# FAN_Boardv1_RelayAlarm_040116.net
KiCad netlist of a schematic drawn in Altium Designer
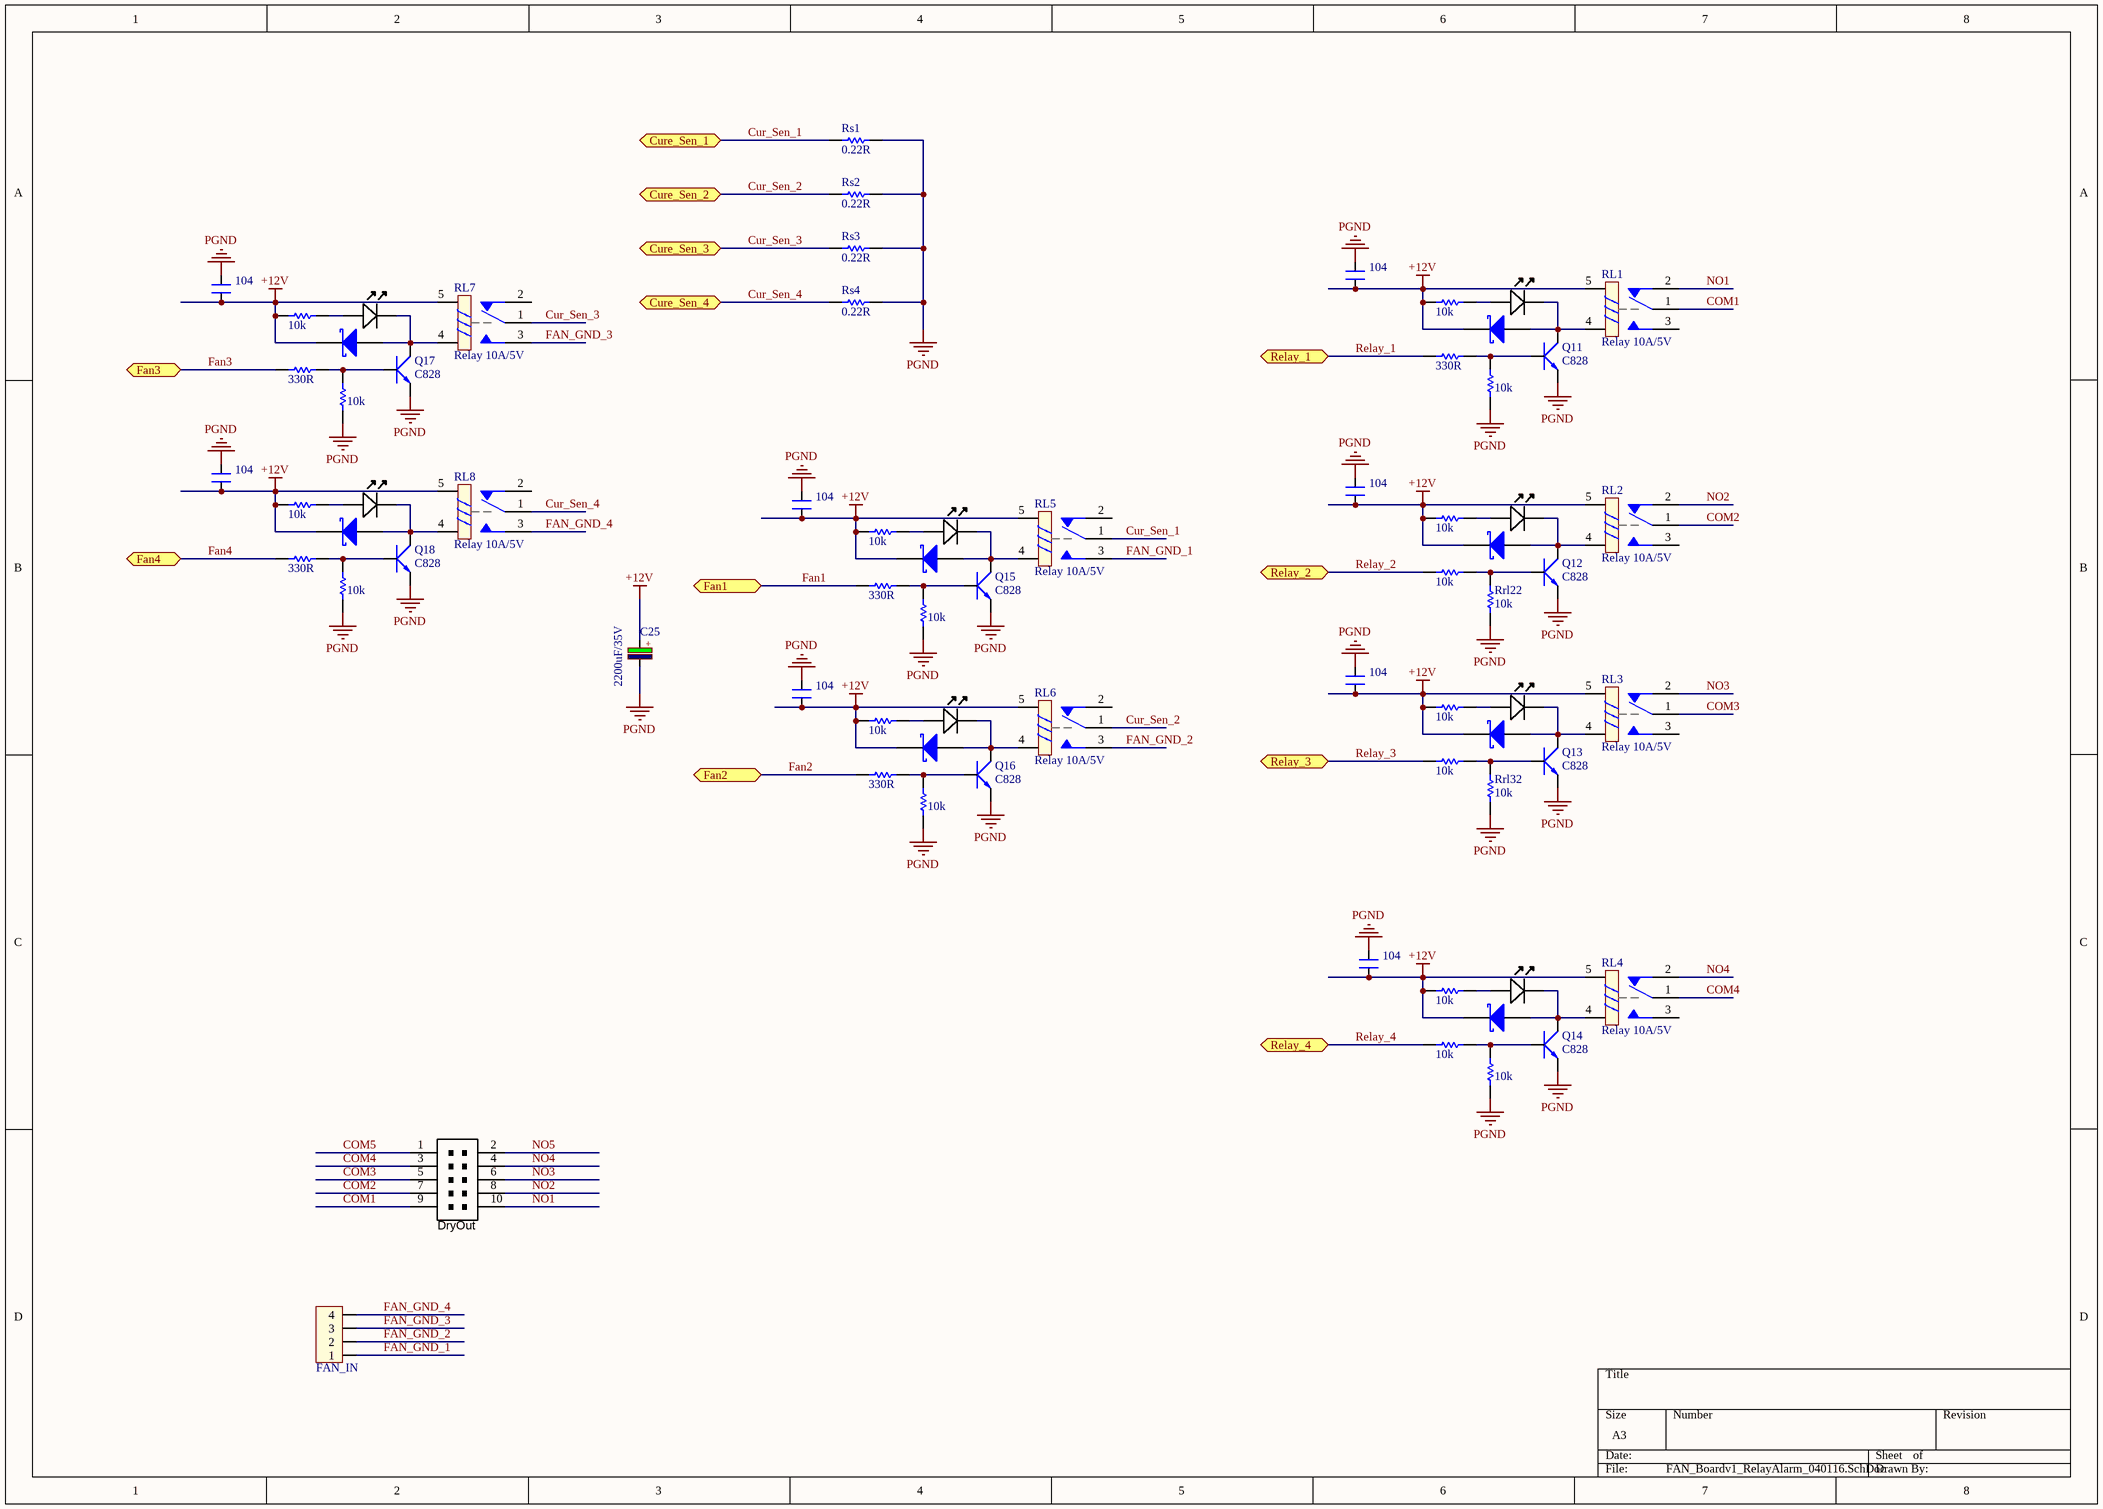
[diagram p0: FAN_Boardv1_RelayAlarm_040116.SchDoc]

(export (version "E")
  (design (tool "Eeschema 10.0.6"))
  (components
    (comp (ref "C25")
      (value "2200uF/35V")
      (footprint "heromap:CP_1000uF_25V")
      (description "Cap 1000uF/16V - 220uF/50V")
      (libsource (lib "heromap") (part "CP4"))
    )
    (comp (ref "Crl1")
      (value "104")
      (footprint "CAPC2012N_F")
      (fields (field (name "Comment") "CAP NP"))
      (libsource (lib "Tuan") (part "CAP NP"))
    )
    (comp (ref "Crl2")
      (value "104")
      (footprint "CAPC2012N_F")
      (fields (field (name "Comment") "CAP NP"))
      (libsource (lib "Tuan") (part "CAP NP"))
    )
    (comp (ref "Crl3")
      (value "104")
      (footprint "CAPC2012N_F")
      (fields (field (name "Comment") "CAP NP"))
      (libsource (lib "Tuan") (part "CAP NP"))
    )
    (comp (ref "Crl4")
      (value "104")
      (footprint "CAPC2012N_F")
      (fields (field (name "Comment") "CAP NP"))
      (libsource (lib "Tuan") (part "CAP NP"))
    )
    (comp (ref "Crl5")
      (value "104")
      (footprint "CAPC2012N_F")
      (fields (field (name "Comment") "CAP NP"))
      (libsource (lib "Tuan") (part "CAP NP"))
    )
    (comp (ref "Crl6")
      (value "104")
      (footprint "CAPC2012N_F")
      (fields (field (name "Comment") "CAP NP"))
      (libsource (lib "Tuan") (part "CAP NP"))
    )
    (comp (ref "Crl7")
      (value "104")
      (footprint "CAPC2012N_F")
      (fields (field (name "Comment") "CAP NP"))
      (libsource (lib "Tuan") (part "CAP NP"))
    )
    (comp (ref "Crl8")
      (value "104")
      (footprint "CAPC2012N_F")
      (fields (field (name "Comment") "CAP NP"))
      (libsource (lib "Tuan") (part "CAP NP"))
    )
    (comp (ref "D11") (value "Diode") (footprint "DO-214AC") (libsource (lib "Tuan") (part "Diode")))
    (comp (ref "D12") (value "Diode") (footprint "DO-214AC") (libsource (lib "Tuan") (part "Diode")))
    (comp (ref "D13") (value "Diode") (footprint "DO-214AC") (libsource (lib "Tuan") (part "Diode")))
    (comp (ref "D14") (value "Diode") (footprint "DO-214AC") (libsource (lib "Tuan") (part "Diode")))
    (comp (ref "D15") (value "Diode") (footprint "DO-214AC") (libsource (lib "Tuan") (part "Diode")))
    (comp (ref "D16") (value "Diode") (footprint "DO-214AC") (libsource (lib "Tuan") (part "Diode")))
    (comp (ref "D17") (value "Diode") (footprint "DO-214AC") (libsource (lib "Tuan") (part "Diode")))
    (comp (ref "D18") (value "Diode") (footprint "DO-214AC") (libsource (lib "Tuan") (part "Diode")))
    (comp (ref "DryOut")
      (value "shrouded box header")
      (footprint "10P_PCB_HEADER_BRD_MNT")
      (description "Header THD 10 POS Double-row 2.54mm pitch")
      (libsource (lib "PBL - Connectors") (part "CONN_HEADER_2x5P_0.100in_Male"))
    )
    (comp (ref "E1")
      (value "Blue")
      (footprint "LED-0805-A")
      (description "LED 0805 SMD Blue 100mcd 470nm")
      (libsource (lib "PBL - Light Sources") (part "LED_SMD_Blue_0805_100mcd"))
    )
    (comp (ref "E2")
      (value "Blue")
      (footprint "LED-0805-A")
      (description "LED 0805 SMD Blue 100mcd 470nm")
      (libsource (lib "PBL - Light Sources") (part "LED_SMD_Blue_0805_100mcd"))
    )
    (comp (ref "E3")
      (value "Blue")
      (footprint "LED-0805-A")
      (description "LED 0805 SMD Blue 100mcd 470nm")
      (libsource (lib "PBL - Light Sources") (part "LED_SMD_Blue_0805_100mcd"))
    )
    (comp (ref "E4")
      (value "Blue")
      (footprint "LED-0805-A")
      (description "LED 0805 SMD Blue 100mcd 470nm")
      (libsource (lib "PBL - Light Sources") (part "LED_SMD_Blue_0805_100mcd"))
    )
    (comp (ref "E5")
      (value "Blue")
      (footprint "LED-0805-A")
      (description "LED 0805 SMD Blue 100mcd 470nm")
      (libsource (lib "PBL - Light Sources") (part "LED_SMD_Blue_0805_100mcd"))
    )
    (comp (ref "E6")
      (value "Blue")
      (footprint "LED-0805-A")
      (description "LED 0805 SMD Blue 100mcd 470nm")
      (libsource (lib "PBL - Light Sources") (part "LED_SMD_Blue_0805_100mcd"))
    )
    (comp (ref "E7")
      (value "Blue")
      (footprint "LED-0805-A")
      (description "LED 0805 SMD Blue 100mcd 470nm")
      (libsource (lib "PBL - Light Sources") (part "LED_SMD_Blue_0805_100mcd"))
    )
    (comp (ref "E8")
      (value "Blue")
      (footprint "LED-0805-A")
      (description "LED 0805 SMD Blue 100mcd 470nm")
      (libsource (lib "PBL - Light Sources") (part "LED_SMD_Blue_0805_100mcd"))
    )
    (comp (ref "FAN_IN")
      (value "Header 4")
      (footprint "heromap:HED4")
      (description "Header 4 (Green)")
      (libsource (lib "heromap") (part "Hed4"))
    )
    (comp (ref "Q11")
      (value "C828")
      (footprint "SOT23 TOP")
      (description "Transistor C828 C1815....")
      (libsource (lib "Tuan") (part "NPN"))
    )
    (comp (ref "Q12")
      (value "C828")
      (footprint "SOT23 TOP")
      (description "Transistor C828 C1815....")
      (libsource (lib "Tuan") (part "NPN"))
    )
    (comp (ref "Q13")
      (value "C828")
      (footprint "SOT23 TOP")
      (description "Transistor C828 C1815....")
      (libsource (lib "Tuan") (part "NPN"))
    )
    (comp (ref "Q14")
      (value "C828")
      (footprint "SOT23 TOP")
      (description "Transistor C828 C1815....")
      (libsource (lib "Tuan") (part "NPN"))
    )
    (comp (ref "Q15")
      (value "C828")
      (footprint "SOT23 TOP")
      (description "Transistor C828 C1815....")
      (libsource (lib "Tuan") (part "NPN"))
    )
    (comp (ref "Q16")
      (value "C828")
      (footprint "SOT23 TOP")
      (description "Transistor C828 C1815....")
      (libsource (lib "Tuan") (part "NPN"))
    )
    (comp (ref "Q17")
      (value "C828")
      (footprint "SOT23 TOP")
      (description "Transistor C828 C1815....")
      (libsource (lib "Tuan") (part "NPN"))
    )
    (comp (ref "Q18")
      (value "C828")
      (footprint "SOT23 TOP")
      (description "Transistor C828 C1815....")
      (libsource (lib "Tuan") (part "NPN"))
    )
    (comp (ref "RL1")
      (value "Relay 10A/5V")
      (footprint "RL_5PIN")
      (description "Relay SPDT,10A - 12VDC 5 Pin")
      (libsource (lib "syhaunguyen") (part "Relay 1"))
    )
    (comp (ref "RL2")
      (value "Relay 10A/5V")
      (footprint "RL_5PIN")
      (description "Relay SPDT,10A - 12VDC 5 Pin")
      (libsource (lib "syhaunguyen") (part "Relay 1"))
    )
    (comp (ref "RL3")
      (value "Relay 10A/5V")
      (footprint "RL_5PIN")
      (description "Relay SPDT,10A - 12VDC 5 Pin")
      (libsource (lib "syhaunguyen") (part "Relay 1"))
    )
    (comp (ref "RL4")
      (value "Relay 10A/5V")
      (footprint "RL_5PIN")
      (description "Relay SPDT,10A - 12VDC 5 Pin")
      (libsource (lib "syhaunguyen") (part "Relay 1"))
    )
    (comp (ref "RL5")
      (value "Relay 10A/5V")
      (footprint "RL_5PIN")
      (description "Relay SPDT,10A - 12VDC 5 Pin")
      (libsource (lib "syhaunguyen") (part "Relay 1"))
    )
    (comp (ref "RL6")
      (value "Relay 10A/5V")
      (footprint "RL_5PIN")
      (description "Relay SPDT,10A - 12VDC 5 Pin")
      (libsource (lib "syhaunguyen") (part "Relay 1"))
    )
    (comp (ref "RL7")
      (value "Relay 10A/5V")
      (footprint "RL_5PIN")
      (description "Relay SPDT,10A - 12VDC 5 Pin")
      (libsource (lib "syhaunguyen") (part "Relay 1"))
    )
    (comp (ref "RL8")
      (value "Relay 10A/5V")
      (footprint "RL_5PIN")
      (description "Relay SPDT,10A - 12VDC 5 Pin")
      (libsource (lib "syhaunguyen") (part "Relay 1"))
    )
    (comp (ref "Rl52")
      (value "10k")
      (footprint "RESC1608N_ZERO")
      (fields (field (name "Comment") "Res"))
      (libsource (lib "Tuan") (part "Res"))
    )
    (comp (ref "Rrl11")
      (value "330R")
      (footprint "RESC1608N_ZERO")
      (fields (field (name "Comment") "Res"))
      (libsource (lib "Tuan") (part "Res"))
    )
    (comp (ref "Rrl12")
      (value "10k")
      (footprint "RESC1608N_ZERO")
      (fields (field (name "Comment") "Res"))
      (libsource (lib "Tuan") (part "Res"))
    )
    (comp (ref "Rrl13")
      (value "10k")
      (footprint "RESC1608N_ZERO")
      (fields (field (name "Comment") "Res"))
      (libsource (lib "Tuan") (part "Res"))
    )
    (comp (ref "Rrl21")
      (value "10k")
      (footprint "RESC1608N_ZERO")
      (fields (field (name "Comment") "Res"))
      (libsource (lib "Tuan") (part "Res"))
    )
    (comp (ref "Rrl22")
      (value "10k")
      (footprint "RESC1608N_ZERO")
      (fields (field (name "Comment") "Res"))
      (libsource (lib "Tuan") (part "Res"))
    )
    (comp (ref "Rrl23")
      (value "10k")
      (footprint "RESC1608N_ZERO")
      (fields (field (name "Comment") "Res"))
      (libsource (lib "Tuan") (part "Res"))
    )
    (comp (ref "Rrl31")
      (value "10k")
      (footprint "RESC1608N_ZERO")
      (fields (field (name "Comment") "Res"))
      (libsource (lib "Tuan") (part "Res"))
    )
    (comp (ref "Rrl32")
      (value "10k")
      (footprint "RESC1608N_ZERO")
      (fields (field (name "Comment") "Res"))
      (libsource (lib "Tuan") (part "Res"))
    )
    (comp (ref "Rrl33")
      (value "10k")
      (footprint "RESC1608N_ZERO")
      (fields (field (name "Comment") "Res"))
      (libsource (lib "Tuan") (part "Res"))
    )
    (comp (ref "Rrl41")
      (value "10k")
      (footprint "RESC1608N_ZERO")
      (fields (field (name "Comment") "Res"))
      (libsource (lib "Tuan") (part "Res"))
    )
    (comp (ref "Rrl42")
      (value "10k")
      (footprint "RESC1608N_ZERO")
      (fields (field (name "Comment") "Res"))
      (libsource (lib "Tuan") (part "Res"))
    )
    (comp (ref "Rrl43")
      (value "10k")
      (footprint "RESC1608N_ZERO")
      (fields (field (name "Comment") "Res"))
      (libsource (lib "Tuan") (part "Res"))
    )
    (comp (ref "Rrl51")
      (value "330R")
      (footprint "RESC1608N_ZERO")
      (fields (field (name "Comment") "Res"))
      (libsource (lib "Tuan") (part "Res"))
    )
    (comp (ref "Rrl53")
      (value "10k")
      (footprint "RESC1608N_ZERO")
      (fields (field (name "Comment") "Res"))
      (libsource (lib "Tuan") (part "Res"))
    )
    (comp (ref "Rrl61")
      (value "330R")
      (footprint "RESC1608N_ZERO")
      (fields (field (name "Comment") "Res"))
      (libsource (lib "Tuan") (part "Res"))
    )
    (comp (ref "Rrl62")
      (value "10k")
      (footprint "RESC1608N_ZERO")
      (fields (field (name "Comment") "Res"))
      (libsource (lib "Tuan") (part "Res"))
    )
    (comp (ref "Rrl63")
      (value "10k")
      (footprint "RESC1608N_ZERO")
      (fields (field (name "Comment") "Res"))
      (libsource (lib "Tuan") (part "Res"))
    )
    (comp (ref "Rrl71")
      (value "330R")
      (footprint "RESC1608N_ZERO")
      (fields (field (name "Comment") "Res"))
      (libsource (lib "Tuan") (part "Res"))
    )
    (comp (ref "Rrl72")
      (value "10k")
      (footprint "RESC1608N_ZERO")
      (fields (field (name "Comment") "Res"))
      (libsource (lib "Tuan") (part "Res"))
    )
    (comp (ref "Rrl73")
      (value "10k")
      (footprint "RESC1608N_ZERO")
      (fields (field (name "Comment") "Res"))
      (libsource (lib "Tuan") (part "Res"))
    )
    (comp (ref "Rrl81")
      (value "330R")
      (footprint "RESC1608N_ZERO")
      (fields (field (name "Comment") "Res"))
      (libsource (lib "Tuan") (part "Res"))
    )
    (comp (ref "Rrl82")
      (value "10k")
      (footprint "RESC1608N_ZERO")
      (fields (field (name "Comment") "Res"))
      (libsource (lib "Tuan") (part "Res"))
    )
    (comp (ref "Rrl83")
      (value "10k")
      (footprint "RESC1608N_ZERO")
      (fields (field (name "Comment") "Res"))
      (libsource (lib "Tuan") (part "Res"))
    )
    (comp (ref "Rs1")
      (value "0.22R")
      (footprint "RESTH_AXIAL-0.4")
      (fields (field (name "Comment") "Res"))
      (libsource (lib "Tuan") (part "Res"))
    )
    (comp (ref "Rs2")
      (value "0.22R")
      (footprint "RESTH_AXIAL-0.4")
      (fields (field (name "Comment") "Res"))
      (libsource (lib "Tuan") (part "Res"))
    )
    (comp (ref "Rs3")
      (value "0.22R")
      (footprint "RESTH_AXIAL-0.4")
      (fields (field (name "Comment") "Res"))
      (libsource (lib "Tuan") (part "Res"))
    )
    (comp (ref "Rs4")
      (value "0.22R")
      (footprint "RESTH_AXIAL-0.4")
      (fields (field (name "Comment") "Res"))
      (libsource (lib "Tuan") (part "Res"))
    )
  )
  (nets
    (net (code "1") (name "+12V") (class "Default")
      (node (ref "C25") (pin "1") (pinfunction "1_1") (pintype "passive"))
      (node (ref "Crl1") (pin "1") (pinfunction "1_1") (pintype "passive"))
      (node (ref "Crl2") (pin "1") (pinfunction "1_1") (pintype "passive"))
      (node (ref "Crl3") (pin "1") (pinfunction "1_1") (pintype "passive"))
      (node (ref "Crl4") (pin "1") (pinfunction "1_1") (pintype "passive"))
      (node (ref "Crl5") (pin "1") (pinfunction "1_1") (pintype "passive"))
      (node (ref "Crl6") (pin "1") (pinfunction "1_1") (pintype "passive"))
      (node (ref "Crl7") (pin "1") (pinfunction "1_1") (pintype "passive"))
      (node (ref "Crl8") (pin "1") (pinfunction "1_1") (pintype "passive"))
      (node (ref "D11") (pin "2") (pinfunction "K_2") (pintype "passive"))
      (node (ref "D12") (pin "2") (pinfunction "K_2") (pintype "passive"))
      (node (ref "D13") (pin "2") (pinfunction "K_2") (pintype "passive"))
      (node (ref "D14") (pin "2") (pinfunction "K_2") (pintype "passive"))
      (node (ref "D15") (pin "2") (pinfunction "K_2") (pintype "passive"))
      (node (ref "D16") (pin "2") (pinfunction "K_2") (pintype "passive"))
      (node (ref "D17") (pin "2") (pinfunction "K_2") (pintype "passive"))
      (node (ref "D18") (pin "2") (pinfunction "K_2") (pintype "passive"))
      (node (ref "RL1") (pin "5") (pinfunction "5_5") (pintype "passive"))
      (node (ref "RL2") (pin "5") (pinfunction "5_5") (pintype "passive"))
      (node (ref "RL3") (pin "5") (pinfunction "5_5") (pintype "passive"))
      (node (ref "RL4") (pin "5") (pinfunction "5_5") (pintype "passive"))
      (node (ref "RL5") (pin "5") (pinfunction "5_5") (pintype "passive"))
      (node (ref "RL6") (pin "5") (pinfunction "5_5") (pintype "passive"))
      (node (ref "RL7") (pin "5") (pinfunction "5_5") (pintype "passive"))
      (node (ref "RL8") (pin "5") (pinfunction "5_5") (pintype "passive"))
      (node (ref "Rrl13") (pin "2") (pinfunction "2_2") (pintype "passive"))
      (node (ref "Rrl23") (pin "2") (pinfunction "2_2") (pintype "passive"))
      (node (ref "Rrl33") (pin "2") (pinfunction "2_2") (pintype "passive"))
      (node (ref "Rrl43") (pin "2") (pinfunction "2_2") (pintype "passive"))
      (node (ref "Rrl53") (pin "2") (pinfunction "2_2") (pintype "passive"))
      (node (ref "Rrl63") (pin "2") (pinfunction "2_2") (pintype "passive"))
      (node (ref "Rrl73") (pin "2") (pinfunction "2_2") (pintype "passive"))
      (node (ref "Rrl83") (pin "2") (pinfunction "2_2") (pintype "passive"))
    )
    (net (code "2") (name "/COM1") (class "Default")
      (node (ref "DryOut") (pin "9") (pinfunction "9_9") (pintype "passive"))
      (node (ref "RL1") (pin "1") (pinfunction "1_1") (pintype "passive"))
    )
    (net (code "3") (name "/COM2") (class "Default")
      (node (ref "DryOut") (pin "7") (pinfunction "7_7") (pintype "passive"))
      (node (ref "RL2") (pin "1") (pinfunction "1_1") (pintype "passive"))
    )
    (net (code "4") (name "/COM3") (class "Default")
      (node (ref "DryOut") (pin "5") (pinfunction "5_5") (pintype "passive"))
      (node (ref "RL3") (pin "1") (pinfunction "1_1") (pintype "passive"))
    )
    (net (code "5") (name "/COM4") (class "Default")
      (node (ref "DryOut") (pin "3") (pinfunction "3_3") (pintype "passive"))
      (node (ref "RL4") (pin "1") (pinfunction "1_1") (pintype "passive"))
    )
    (net (code "6") (name "/COM5") (class "Default")
      (node (ref "DryOut") (pin "1") (pinfunction "1_1") (pintype "passive"))
    )
    (net (code "7") (name "/Cur_Sen_1") (class "Default")
      (node (ref "RL5") (pin "1") (pinfunction "1_1") (pintype "passive"))
      (node (ref "Rs1") (pin "2") (pinfunction "2_2") (pintype "passive"))
    )
    (net (code "8") (name "/Cur_Sen_2") (class "Default")
      (node (ref "RL6") (pin "1") (pinfunction "1_1") (pintype "passive"))
      (node (ref "Rs2") (pin "2") (pinfunction "2_2") (pintype "passive"))
    )
    (net (code "9") (name "/Cur_Sen_3") (class "Default")
      (node (ref "RL7") (pin "1") (pinfunction "1_1") (pintype "passive"))
      (node (ref "Rs3") (pin "2") (pinfunction "2_2") (pintype "passive"))
    )
    (net (code "10") (name "/Cur_Sen_4") (class "Default")
      (node (ref "RL8") (pin "1") (pinfunction "1_1") (pintype "passive"))
      (node (ref "Rs4") (pin "2") (pinfunction "2_2") (pintype "passive"))
    )
    (net (code "11") (name "/FAN_GND_1") (class "Default")
      (node (ref "FAN_IN") (pin "1") (pinfunction "1_1") (pintype "passive"))
      (node (ref "RL5") (pin "3") (pinfunction "3_3") (pintype "passive"))
    )
    (net (code "12") (name "/FAN_GND_2") (class "Default")
      (node (ref "FAN_IN") (pin "2") (pinfunction "2_2") (pintype "passive"))
      (node (ref "RL6") (pin "3") (pinfunction "3_3") (pintype "passive"))
    )
    (net (code "13") (name "/FAN_GND_3") (class "Default")
      (node (ref "FAN_IN") (pin "3") (pinfunction "3_3") (pintype "passive"))
      (node (ref "RL7") (pin "3") (pinfunction "3_3") (pintype "passive"))
    )
    (net (code "14") (name "/FAN_GND_4") (class "Default")
      (node (ref "FAN_IN") (pin "4") (pinfunction "4_4") (pintype "passive"))
      (node (ref "RL8") (pin "3") (pinfunction "3_3") (pintype "passive"))
    )
    (net (code "15") (name "/Fan1") (class "Default")
      (node (ref "Rrl51") (pin "1") (pinfunction "1_1") (pintype "passive"))
    )
    (net (code "16") (name "/Fan2") (class "Default")
      (node (ref "Rrl61") (pin "1") (pinfunction "1_1") (pintype "passive"))
    )
    (net (code "17") (name "/Fan3") (class "Default")
      (node (ref "Rrl71") (pin "1") (pinfunction "1_1") (pintype "passive"))
    )
    (net (code "18") (name "/Fan4") (class "Default")
      (node (ref "Rrl81") (pin "1") (pinfunction "1_1") (pintype "passive"))
    )
    (net (code "19") (name "/NO1") (class "Default")
      (node (ref "DryOut") (pin "10") (pinfunction "10_10") (pintype "passive"))
      (node (ref "RL1") (pin "2") (pinfunction "2_2") (pintype "passive"))
    )
    (net (code "20") (name "/NO2") (class "Default")
      (node (ref "DryOut") (pin "8") (pinfunction "8_8") (pintype "passive"))
      (node (ref "RL2") (pin "2") (pinfunction "2_2") (pintype "passive"))
    )
    (net (code "21") (name "/NO3") (class "Default")
      (node (ref "DryOut") (pin "6") (pinfunction "6_6") (pintype "passive"))
      (node (ref "RL3") (pin "2") (pinfunction "2_2") (pintype "passive"))
    )
    (net (code "22") (name "/NO4") (class "Default")
      (node (ref "DryOut") (pin "4") (pinfunction "4_4") (pintype "passive"))
      (node (ref "RL4") (pin "2") (pinfunction "2_2") (pintype "passive"))
    )
    (net (code "23") (name "/NO5") (class "Default")
      (node (ref "DryOut") (pin "2") (pinfunction "2_2") (pintype "passive"))
    )
    (net (code "24") (name "/Relay_1") (class "Default")
      (node (ref "Rrl11") (pin "1") (pinfunction "1_1") (pintype "passive"))
    )
    (net (code "25") (name "/Relay_2") (class "Default")
      (node (ref "Rrl21") (pin "1") (pinfunction "1_1") (pintype "passive"))
    )
    (net (code "26") (name "/Relay_3") (class "Default")
      (node (ref "Rrl31") (pin "1") (pinfunction "1_1") (pintype "passive"))
    )
    (net (code "27") (name "/Relay_4") (class "Default")
      (node (ref "Rrl41") (pin "1") (pinfunction "1_1") (pintype "passive"))
    )
    (net (code "28") (name "Net-(D11-A)") (class "Default")
      (node (ref "D11") (pin "1") (pinfunction "A_1") (pintype "passive"))
      (node (ref "E1") (pin "K") (pinfunction "K_K") (pintype "passive"))
      (node (ref "Q11") (pin "2") (pinfunction "C_2") (pintype "passive"))
      (node (ref "RL1") (pin "4") (pinfunction "4_4") (pintype "passive"))
    )
    (net (code "29") (name "Net-(D12-A)") (class "Default")
      (node (ref "D12") (pin "1") (pinfunction "A_1") (pintype "passive"))
      (node (ref "E2") (pin "K") (pinfunction "K_K") (pintype "passive"))
      (node (ref "Q12") (pin "2") (pinfunction "C_2") (pintype "passive"))
      (node (ref "RL2") (pin "4") (pinfunction "4_4") (pintype "passive"))
    )
    (net (code "30") (name "Net-(D13-A)") (class "Default")
      (node (ref "D13") (pin "1") (pinfunction "A_1") (pintype "passive"))
      (node (ref "E3") (pin "K") (pinfunction "K_K") (pintype "passive"))
      (node (ref "Q13") (pin "2") (pinfunction "C_2") (pintype "passive"))
      (node (ref "RL3") (pin "4") (pinfunction "4_4") (pintype "passive"))
    )
    (net (code "31") (name "Net-(D14-A)") (class "Default")
      (node (ref "D14") (pin "1") (pinfunction "A_1") (pintype "passive"))
      (node (ref "E4") (pin "K") (pinfunction "K_K") (pintype "passive"))
      (node (ref "Q14") (pin "2") (pinfunction "C_2") (pintype "passive"))
      (node (ref "RL4") (pin "4") (pinfunction "4_4") (pintype "passive"))
    )
    (net (code "32") (name "Net-(D15-A)") (class "Default")
      (node (ref "D15") (pin "1") (pinfunction "A_1") (pintype "passive"))
      (node (ref "E5") (pin "K") (pinfunction "K_K") (pintype "passive"))
      (node (ref "Q15") (pin "2") (pinfunction "C_2") (pintype "passive"))
      (node (ref "RL5") (pin "4") (pinfunction "4_4") (pintype "passive"))
    )
    (net (code "33") (name "Net-(D16-A)") (class "Default")
      (node (ref "D16") (pin "1") (pinfunction "A_1") (pintype "passive"))
      (node (ref "E6") (pin "K") (pinfunction "K_K") (pintype "passive"))
      (node (ref "Q16") (pin "2") (pinfunction "C_2") (pintype "passive"))
      (node (ref "RL6") (pin "4") (pinfunction "4_4") (pintype "passive"))
    )
    (net (code "34") (name "Net-(D17-A)") (class "Default")
      (node (ref "D17") (pin "1") (pinfunction "A_1") (pintype "passive"))
      (node (ref "E7") (pin "K") (pinfunction "K_K") (pintype "passive"))
      (node (ref "Q17") (pin "2") (pinfunction "C_2") (pintype "passive"))
      (node (ref "RL7") (pin "4") (pinfunction "4_4") (pintype "passive"))
    )
    (net (code "35") (name "Net-(D18-A)") (class "Default")
      (node (ref "D18") (pin "1") (pinfunction "A_1") (pintype "passive"))
      (node (ref "E8") (pin "K") (pinfunction "K_K") (pintype "passive"))
      (node (ref "Q18") (pin "2") (pinfunction "C_2") (pintype "passive"))
      (node (ref "RL8") (pin "4") (pinfunction "4_4") (pintype "passive"))
    )
    (net (code "36") (name "Net-(E1-PadA)") (class "Default")
      (node (ref "E1") (pin "A") (pinfunction "A_A") (pintype "passive"))
      (node (ref "Rrl13") (pin "1") (pinfunction "1_1") (pintype "passive"))
    )
    (net (code "37") (name "Net-(E2-PadA)") (class "Default")
      (node (ref "E2") (pin "A") (pinfunction "A_A") (pintype "passive"))
      (node (ref "Rrl23") (pin "1") (pinfunction "1_1") (pintype "passive"))
    )
    (net (code "38") (name "Net-(E3-PadA)") (class "Default")
      (node (ref "E3") (pin "A") (pinfunction "A_A") (pintype "passive"))
      (node (ref "Rrl33") (pin "1") (pinfunction "1_1") (pintype "passive"))
    )
    (net (code "39") (name "Net-(E4-PadA)") (class "Default")
      (node (ref "E4") (pin "A") (pinfunction "A_A") (pintype "passive"))
      (node (ref "Rrl43") (pin "1") (pinfunction "1_1") (pintype "passive"))
    )
    (net (code "40") (name "Net-(E5-PadA)") (class "Default")
      (node (ref "E5") (pin "A") (pinfunction "A_A") (pintype "passive"))
      (node (ref "Rrl53") (pin "1") (pinfunction "1_1") (pintype "passive"))
    )
    (net (code "41") (name "Net-(E6-PadA)") (class "Default")
      (node (ref "E6") (pin "A") (pinfunction "A_A") (pintype "passive"))
      (node (ref "Rrl63") (pin "1") (pinfunction "1_1") (pintype "passive"))
    )
    (net (code "42") (name "Net-(E7-PadA)") (class "Default")
      (node (ref "E7") (pin "A") (pinfunction "A_A") (pintype "passive"))
      (node (ref "Rrl73") (pin "1") (pinfunction "1_1") (pintype "passive"))
    )
    (net (code "43") (name "Net-(E8-PadA)") (class "Default")
      (node (ref "E8") (pin "A") (pinfunction "A_A") (pintype "passive"))
      (node (ref "Rrl83") (pin "1") (pinfunction "1_1") (pintype "passive"))
    )
    (net (code "44") (name "Net-(Q11-B)") (class "Default")
      (node (ref "Q11") (pin "1") (pinfunction "B_1") (pintype "passive"))
      (node (ref "Rrl11") (pin "2") (pinfunction "2_2") (pintype "passive"))
      (node (ref "Rrl12") (pin "2") (pinfunction "2_2") (pintype "passive"))
    )
    (net (code "45") (name "Net-(Q12-B)") (class "Default")
      (node (ref "Q12") (pin "1") (pinfunction "B_1") (pintype "passive"))
      (node (ref "Rrl21") (pin "2") (pinfunction "2_2") (pintype "passive"))
      (node (ref "Rrl22") (pin "2") (pinfunction "2_2") (pintype "passive"))
    )
    (net (code "46") (name "Net-(Q13-B)") (class "Default")
      (node (ref "Q13") (pin "1") (pinfunction "B_1") (pintype "passive"))
      (node (ref "Rrl31") (pin "2") (pinfunction "2_2") (pintype "passive"))
      (node (ref "Rrl32") (pin "2") (pinfunction "2_2") (pintype "passive"))
    )
    (net (code "47") (name "Net-(Q14-B)") (class "Default")
      (node (ref "Q14") (pin "1") (pinfunction "B_1") (pintype "passive"))
      (node (ref "Rrl41") (pin "2") (pinfunction "2_2") (pintype "passive"))
      (node (ref "Rrl42") (pin "2") (pinfunction "2_2") (pintype "passive"))
    )
    (net (code "48") (name "Net-(Q15-B)") (class "Default")
      (node (ref "Q15") (pin "1") (pinfunction "B_1") (pintype "passive"))
      (node (ref "Rl52") (pin "2") (pinfunction "2_2") (pintype "passive"))
      (node (ref "Rrl51") (pin "2") (pinfunction "2_2") (pintype "passive"))
    )
    (net (code "49") (name "Net-(Q16-B)") (class "Default")
      (node (ref "Q16") (pin "1") (pinfunction "B_1") (pintype "passive"))
      (node (ref "Rrl61") (pin "2") (pinfunction "2_2") (pintype "passive"))
      (node (ref "Rrl62") (pin "2") (pinfunction "2_2") (pintype "passive"))
    )
    (net (code "50") (name "Net-(Q17-B)") (class "Default")
      (node (ref "Q17") (pin "1") (pinfunction "B_1") (pintype "passive"))
      (node (ref "Rrl71") (pin "2") (pinfunction "2_2") (pintype "passive"))
      (node (ref "Rrl72") (pin "2") (pinfunction "2_2") (pintype "passive"))
    )
    (net (code "51") (name "Net-(Q18-B)") (class "Default")
      (node (ref "Q18") (pin "1") (pinfunction "B_1") (pintype "passive"))
      (node (ref "Rrl81") (pin "2") (pinfunction "2_2") (pintype "passive"))
      (node (ref "Rrl82") (pin "2") (pinfunction "2_2") (pintype "passive"))
    )
    (net (code "52") (name "PGND") (class "Default")
      (node (ref "C25") (pin "2") (pinfunction "2_2") (pintype "passive"))
      (node (ref "Crl1") (pin "2") (pinfunction "2_2") (pintype "passive"))
      (node (ref "Crl2") (pin "2") (pinfunction "2_2") (pintype "passive"))
      (node (ref "Crl3") (pin "2") (pinfunction "2_2") (pintype "passive"))
      (node (ref "Crl4") (pin "2") (pinfunction "2_2") (pintype "passive"))
      (node (ref "Crl5") (pin "2") (pinfunction "2_2") (pintype "passive"))
      (node (ref "Crl6") (pin "2") (pinfunction "2_2") (pintype "passive"))
      (node (ref "Crl7") (pin "2") (pinfunction "2_2") (pintype "passive"))
      (node (ref "Crl8") (pin "2") (pinfunction "2_2") (pintype "passive"))
      (node (ref "Q11") (pin "3") (pinfunction "E_3") (pintype "passive"))
      (node (ref "Q12") (pin "3") (pinfunction "E_3") (pintype "passive"))
      (node (ref "Q13") (pin "3") (pinfunction "E_3") (pintype "passive"))
      (node (ref "Q14") (pin "3") (pinfunction "E_3") (pintype "passive"))
      (node (ref "Q15") (pin "3") (pinfunction "E_3") (pintype "passive"))
      (node (ref "Q16") (pin "3") (pinfunction "E_3") (pintype "passive"))
      (node (ref "Q17") (pin "3") (pinfunction "E_3") (pintype "passive"))
      (node (ref "Q18") (pin "3") (pinfunction "E_3") (pintype "passive"))
      (node (ref "Rl52") (pin "1") (pinfunction "1_1") (pintype "passive"))
      (node (ref "Rrl12") (pin "1") (pinfunction "1_1") (pintype "passive"))
      (node (ref "Rrl22") (pin "1") (pinfunction "1_1") (pintype "passive"))
      (node (ref "Rrl32") (pin "1") (pinfunction "1_1") (pintype "passive"))
      (node (ref "Rrl42") (pin "1") (pinfunction "1_1") (pintype "passive"))
      (node (ref "Rrl62") (pin "1") (pinfunction "1_1") (pintype "passive"))
      (node (ref "Rrl72") (pin "1") (pinfunction "1_1") (pintype "passive"))
      (node (ref "Rrl82") (pin "1") (pinfunction "1_1") (pintype "passive"))
      (node (ref "Rs1") (pin "1") (pinfunction "1_1") (pintype "passive"))
      (node (ref "Rs2") (pin "1") (pinfunction "1_1") (pintype "passive"))
      (node (ref "Rs3") (pin "1") (pinfunction "1_1") (pintype "passive"))
      (node (ref "Rs4") (pin "1") (pinfunction "1_1") (pintype "passive"))
    )
    (net (code "53") (name "unconnected-(RL1-Pad3)") (class "Default")
      (node (ref "RL1") (pin "3") (pinfunction "3_3") (pintype "passive"))
    )
    (net (code "54") (name "unconnected-(RL2-Pad3)") (class "Default")
      (node (ref "RL2") (pin "3") (pinfunction "3_3") (pintype "passive"))
    )
    (net (code "55") (name "unconnected-(RL3-Pad3)") (class "Default")
      (node (ref "RL3") (pin "3") (pinfunction "3_3") (pintype "passive"))
    )
    (net (code "56") (name "unconnected-(RL4-Pad3)") (class "Default")
      (node (ref "RL4") (pin "3") (pinfunction "3_3") (pintype "passive"))
    )
    (net (code "57") (name "unconnected-(RL5-Pad2)") (class "Default")
      (node (ref "RL5") (pin "2") (pinfunction "2_2") (pintype "passive"))
    )
    (net (code "58") (name "unconnected-(RL6-Pad2)") (class "Default")
      (node (ref "RL6") (pin "2") (pinfunction "2_2") (pintype "passive"))
    )
    (net (code "59") (name "unconnected-(RL7-Pad2)") (class "Default")
      (node (ref "RL7") (pin "2") (pinfunction "2_2") (pintype "passive"))
    )
    (net (code "60") (name "unconnected-(RL8-Pad2)") (class "Default")
      (node (ref "RL8") (pin "2") (pinfunction "2_2") (pintype "passive"))
    )
  )
)
